# 3_AUDIO.net
KiCad netlist of a schematic drawn in Altium Designer
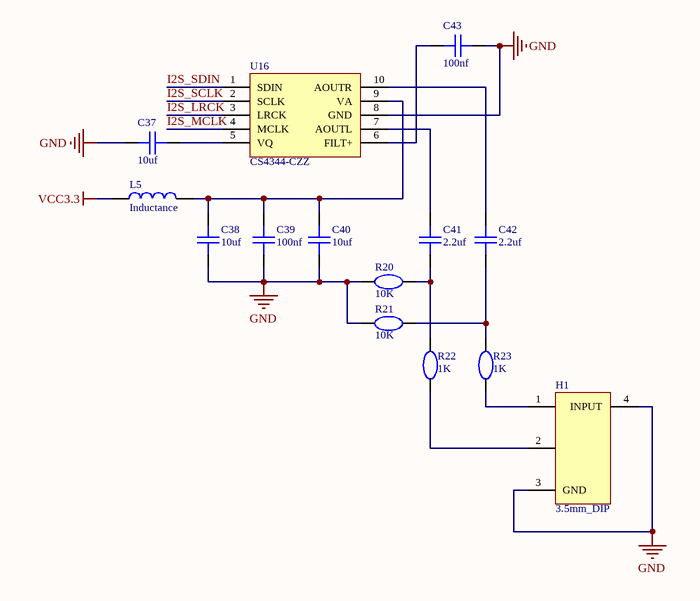
[diagram p0: 3_AUDIO.schdoc]

(export (version "E")
  (design (tool "Eeschema 10.0.6"))
  (components
    (comp (ref "C37") (value "10uf") (footprint "3216") (libsource (lib "sch") (part "CAP")))
    (comp (ref "C38") (value "10uf") (footprint "3216") (libsource (lib "sch") (part "CAP")))
    (comp (ref "C39") (value "100nf") (footprint "3216") (libsource (lib "sch") (part "CAP")))
    (comp (ref "C40") (value "10uf") (footprint "3216") (libsource (lib "sch") (part "CAP")))
    (comp (ref "C41") (value "2.2uf") (footprint "0805") (libsource (lib "sch") (part "CAP")))
    (comp (ref "C42") (value "2.2uf") (footprint "0805") (libsource (lib "sch") (part "CAP")))
    (comp (ref "C43") (value "100nf") (footprint "3216") (libsource (lib "sch") (part "CAP")))
    (comp (ref "H1") (value "3.5mm_DIP") (footprint "PJ320D") (libsource (lib "sch") (part "3.5mm_DIP")))
    (comp (ref "L5") (value "Inductance") (footprint "0805") (libsource (lib "sch") (part "Inductance")))
    (comp (ref "R20") (value "10K") (footprint "0402R") (libsource (lib "sch") (part "RST")))
    (comp (ref "R21") (value "10K") (footprint "0402R") (libsource (lib "sch") (part "RST")))
    (comp (ref "R22") (value "1K") (footprint "0402R") (libsource (lib "sch") (part "RST")))
    (comp (ref "R23") (value "1K") (footprint "0402R") (libsource (lib "sch") (part "RST")))
    (comp (ref "U16")
      (value "CS4344-CZZ")
      (footprint "TSSOP-10_L3.0-W3.0-P0.50-LS4.9-BL")
      (libsource (lib "sch") (part "CS4344-CZZ"))
    )
  )
  (nets
    (net (code "1") (name "/I2S_LRCK") (class "Default")
      (node (ref "U16") (pin "3") (pinfunction "LRCK_3") (pintype "passive"))
    )
    (net (code "2") (name "/I2S_MCLK") (class "Default")
      (node (ref "U16") (pin "4") (pinfunction "MCLK_4") (pintype "passive"))
    )
    (net (code "3") (name "/I2S_SCLK") (class "Default")
      (node (ref "U16") (pin "2") (pinfunction "SCLK_2") (pintype "passive"))
    )
    (net (code "4") (name "/I2S_SDIN") (class "Default")
      (node (ref "U16") (pin "1") (pinfunction "SDIN_1") (pintype "passive"))
    )
    (net (code "5") (name "GND") (class "Default")
      (node (ref "C37") (pin "2") (pinfunction "2_2") (pintype "passive"))
      (node (ref "C38") (pin "2") (pinfunction "2_2") (pintype "passive"))
      (node (ref "C39") (pin "2") (pinfunction "2_2") (pintype "passive"))
      (node (ref "C40") (pin "2") (pinfunction "2_2") (pintype "passive"))
      (node (ref "C43") (pin "2") (pinfunction "2_2") (pintype "passive"))
      (node (ref "H1") (pin "3") (pinfunction "GND_3") (pintype "passive"))
      (node (ref "H1") (pin "4") (pinfunction "INPUT_4") (pintype "passive"))
      (node (ref "R20") (pin "2") (pinfunction "2_2") (pintype "passive"))
      (node (ref "R21") (pin "2") (pinfunction "2_2") (pintype "passive"))
      (node (ref "U16") (pin "8") (pinfunction "GND_8") (pintype "passive"))
    )
    (net (code "6") (name "Net-(C41-Pad2)") (class "Default")
      (node (ref "C41") (pin "2") (pinfunction "2_2") (pintype "passive"))
      (node (ref "R20") (pin "1") (pinfunction "1_1") (pintype "passive"))
      (node (ref "R22") (pin "1") (pinfunction "1_1") (pintype "passive"))
    )
    (net (code "7") (name "Net-(C42-Pad2)") (class "Default")
      (node (ref "C42") (pin "2") (pinfunction "2_2") (pintype "passive"))
      (node (ref "R21") (pin "1") (pinfunction "1_1") (pintype "passive"))
      (node (ref "R23") (pin "1") (pinfunction "1_1") (pintype "passive"))
    )
    (net (code "8") (name "Net-(H1-Pad1)") (class "Default")
      (node (ref "H1") (pin "1") (pintype "passive"))
      (node (ref "R23") (pin "2") (pinfunction "2_2") (pintype "passive"))
    )
    (net (code "9") (name "Net-(H1-Pad2)") (class "Default")
      (node (ref "H1") (pin "2") (pintype "passive"))
      (node (ref "R22") (pin "2") (pinfunction "2_2") (pintype "passive"))
    )
    (net (code "10") (name "Net-(U16-AOUTL)") (class "Default")
      (node (ref "C41") (pin "1") (pinfunction "1_1") (pintype "passive"))
      (node (ref "U16") (pin "7") (pinfunction "AOUTL_7") (pintype "passive"))
    )
    (net (code "11") (name "Net-(U16-AOUTR)") (class "Default")
      (node (ref "C42") (pin "1") (pinfunction "1_1") (pintype "passive"))
      (node (ref "U16") (pin "10") (pinfunction "AOUTR_10") (pintype "passive"))
    )
    (net (code "12") (name "Net-(U16-FILT+)") (class "Default")
      (node (ref "C43") (pin "1") (pinfunction "1_1") (pintype "passive"))
      (node (ref "U16") (pin "6") (pinfunction "FILT+_6") (pintype "passive"))
    )
    (net (code "13") (name "Net-(U16-VA)") (class "Default")
      (node (ref "C38") (pin "1") (pinfunction "1_1") (pintype "passive"))
      (node (ref "C39") (pin "1") (pinfunction "1_1") (pintype "passive"))
      (node (ref "C40") (pin "1") (pinfunction "1_1") (pintype "passive"))
      (node (ref "L5") (pin "2") (pinfunction "2_2") (pintype "passive"))
      (node (ref "U16") (pin "9") (pinfunction "VA_9") (pintype "passive"))
    )
    (net (code "14") (name "Net-(U16-VQ)") (class "Default")
      (node (ref "C37") (pin "1") (pinfunction "1_1") (pintype "passive"))
      (node (ref "U16") (pin "5") (pinfunction "VQ_5") (pintype "passive"))
    )
    (net (code "15") (name "VCC3.3") (class "Default")
      (node (ref "L5") (pin "1") (pinfunction "1_1") (pintype "passive"))
    )
  )
)
